# ES_3340_6HP_Rev_3.net
KiCad netlist of a schematic drawn in EAGLE
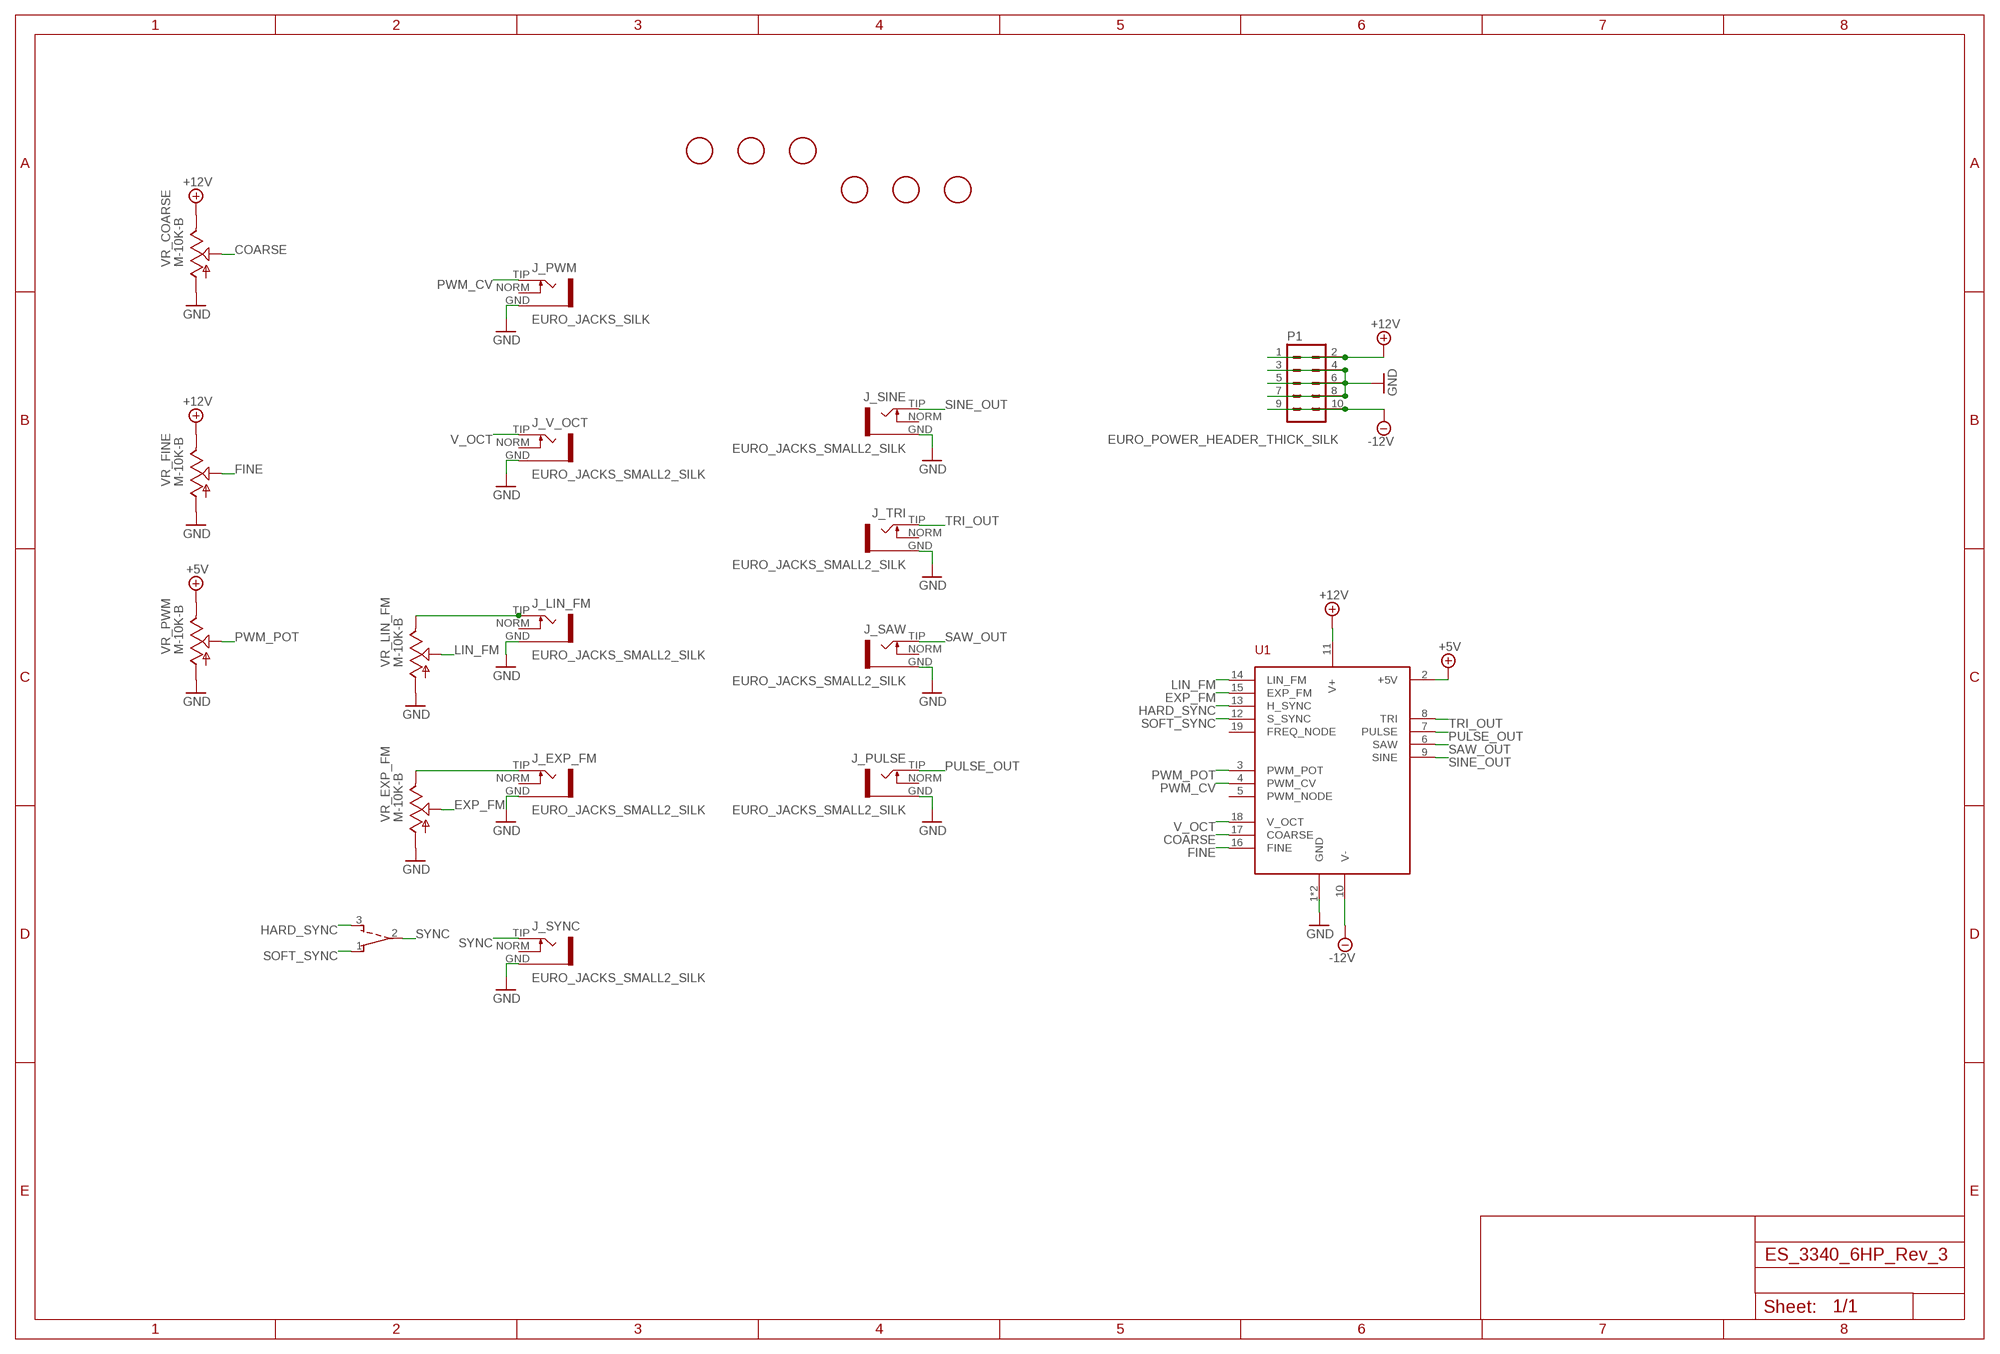
[diagram p0: schematic, sheet 1]

(export (version "E")
  (design (tool "Eeschema 10.0.6"))
  (components
    (comp (ref "FD1")
      (value "FIDUCIAL")
      (footprint "eagle-import:FIDUCIAL_1MM")
      (libsource (lib "eagle-import") (part "FIDUCIAL"))
    )
    (comp (ref "FD2")
      (value "FIDUCIAL")
      (footprint "eagle-import:FIDUCIAL_1MM")
      (libsource (lib "eagle-import") (part "FIDUCIAL"))
    )
    (comp (ref "FD3")
      (value "FIDUCIAL")
      (footprint "eagle-import:FIDUCIAL_1MM")
      (libsource (lib "eagle-import") (part "FIDUCIAL"))
    )
    (comp (ref "FD4")
      (value "FIDUCIAL")
      (footprint "eagle-import:FIDUCIAL_1MM")
      (libsource (lib "eagle-import") (part "FIDUCIAL"))
    )
    (comp (ref "FD5")
      (value "FIDUCIAL")
      (footprint "eagle-import:FIDUCIAL_1MM")
      (libsource (lib "eagle-import") (part "FIDUCIAL"))
    )
    (comp (ref "FD6")
      (value "FIDUCIAL")
      (footprint "eagle-import:FIDUCIAL_1MM")
      (libsource (lib "eagle-import") (part "FIDUCIAL"))
    )
    (comp (ref "J_EXP_FM")
      (value "EURO_JACKS_SMALL2_SILK")
      (footprint "eagle-import:S_JACK_SMALL2_SILK")
      (libsource (lib "eagle-import") (part "EURO_JACKS_SMALL2_SILK"))
    )
    (comp (ref "J_LIN_FM")
      (value "EURO_JACKS_SMALL2_SILK")
      (footprint "eagle-import:S_JACK_SMALL2_SILK")
      (libsource (lib "eagle-import") (part "EURO_JACKS_SMALL2_SILK"))
    )
    (comp (ref "J_PULSE")
      (value "EURO_JACKS_SMALL2_SILK")
      (footprint "eagle-import:S_JACK_SMALL2_SILK")
      (libsource (lib "eagle-import") (part "EURO_JACKS_SMALL2_SILK"))
    )
    (comp (ref "J_PWM")
      (value "EURO_JACKS_SILK")
      (footprint "eagle-import:S_JACK_SILK")
      (libsource (lib "eagle-import") (part "EURO_JACKS_SILK"))
    )
    (comp (ref "J_SAW")
      (value "EURO_JACKS_SMALL2_SILK")
      (footprint "eagle-import:S_JACK_SMALL2_SILK")
      (libsource (lib "eagle-import") (part "EURO_JACKS_SMALL2_SILK"))
    )
    (comp (ref "J_SINE")
      (value "EURO_JACKS_SMALL2_SILK")
      (footprint "eagle-import:S_JACK_SMALL2_SILK")
      (libsource (lib "eagle-import") (part "EURO_JACKS_SMALL2_SILK"))
    )
    (comp (ref "J_SYNC")
      (value "EURO_JACKS_SMALL2_SILK")
      (footprint "eagle-import:S_JACK_SMALL2_SILK")
      (libsource (lib "eagle-import") (part "EURO_JACKS_SMALL2_SILK"))
    )
    (comp (ref "J_TRI")
      (value "EURO_JACKS_SMALL2_SILK")
      (footprint "eagle-import:S_JACK_SMALL2_SILK")
      (libsource (lib "eagle-import") (part "EURO_JACKS_SMALL2_SILK"))
    )
    (comp (ref "J_V_OCT")
      (value "EURO_JACKS_SMALL2_SILK")
      (footprint "eagle-import:S_JACK_SMALL2_SILK")
      (libsource (lib "eagle-import") (part "EURO_JACKS_SMALL2_SILK"))
    )
    (comp (ref "P1")
      (value "EURO_POWER_HEADER_THICK_SILK")
      (footprint "eagle-import:2X5_LOCK")
      (libsource (lib "eagle-import") (part "EURO_POWER_HEADER_THICK_SILK"))
    )
    (comp (ref "SW1")
      (value "TOGGLE_ON-ON")
      (footprint "eagle-import:TOGGLE_ON-ON")
      (libsource (lib "eagle-import") (part "TOGGLE_ON-ON"))
    )
    (comp (ref "U1")
      (value "ES_3340_V2")
      (footprint "eagle-import:ES_3340_V2")
      (libsource (lib "eagle-import") (part "ES_3340_V2"))
    )
    (comp (ref "VR_COARSE")
      (value "M-10K-B")
      (footprint "eagle-import:9MM_SNAP-IN_POT_SILK")
      (libsource (lib "eagle-import") (part "POT_9MM_SNAP-IN__"))
    )
    (comp (ref "VR_EXP_FM")
      (value "M-10K-B")
      (footprint "eagle-import:9MM_SNAP-IN_POT_SILK")
      (libsource (lib "eagle-import") (part "POT_9MM_SNAP-IN__"))
    )
    (comp (ref "VR_FINE")
      (value "M-10K-B")
      (footprint "eagle-import:9MM_SNAP-IN_POT_SILK")
      (libsource (lib "eagle-import") (part "POT_9MM_SNAP-IN__"))
    )
    (comp (ref "VR_LIN_FM")
      (value "M-10K-B")
      (footprint "eagle-import:9MM_SNAP-IN_POT_SILK")
      (libsource (lib "eagle-import") (part "POT_9MM_SNAP-IN__"))
    )
    (comp (ref "VR_PWM")
      (value "M-10K-B")
      (footprint "eagle-import:9MM_SNAP-IN_POT_SILK")
      (libsource (lib "eagle-import") (part "POT_9MM_SNAP-IN__"))
    )
  )
  (nets
    (net (code "1") (name "+5V") (class "Default")
      (node (ref "U1") (pin "2") (pinfunction "+5V_2") (pintype "bidirectional"))
      (node (ref "VR_PWM") (pin "3") (pinfunction "3_3") (pintype "passive"))
    )
    (net (code "2") (name "+12V") (class "Default")
      (node (ref "P1") (pin "1") (pinfunction "10_1") (pintype "bidirectional"))
      (node (ref "P1") (pin "2") (pinfunction "9_2") (pintype "bidirectional"))
      (node (ref "U1") (pin "11") (pinfunction "V+_11") (pintype "bidirectional"))
      (node (ref "VR_COARSE") (pin "3") (pinfunction "3_3") (pintype "passive"))
      (node (ref "VR_FINE") (pin "3") (pinfunction "3_3") (pintype "passive"))
    )
    (net (code "3") (name "-12V") (class "Default")
      (node (ref "P1") (pin "10") (pinfunction "1_10") (pintype "bidirectional"))
      (node (ref "P1") (pin "9") (pinfunction "2_9") (pintype "bidirectional"))
      (node (ref "U1") (pin "10") (pinfunction "V-_10") (pintype "bidirectional"))
    )
    (net (code "4") (name "/COARSE") (class "Default")
      (node (ref "U1") (pin "17") (pinfunction "COARSE_17") (pintype "bidirectional"))
      (node (ref "VR_COARSE") (pin "2") (pinfunction "2_2") (pintype "passive"))
    )
    (net (code "5") (name "/EXP_FM") (class "Default")
      (node (ref "U1") (pin "15") (pinfunction "EXP_FM_15") (pintype "bidirectional"))
      (node (ref "VR_EXP_FM") (pin "2") (pinfunction "2_2") (pintype "passive"))
    )
    (net (code "6") (name "/FINE") (class "Default")
      (node (ref "U1") (pin "16") (pinfunction "FINE_16") (pintype "bidirectional"))
      (node (ref "VR_FINE") (pin "2") (pinfunction "2_2") (pintype "passive"))
    )
    (net (code "7") (name "/HARD_SYNC") (class "Default")
      (node (ref "SW1") (pin "3") (pinfunction "S_3") (pintype "passive"))
      (node (ref "U1") (pin "13") (pinfunction "H_SYNC_13") (pintype "bidirectional"))
    )
    (net (code "8") (name "/LIN_FM") (class "Default")
      (node (ref "U1") (pin "14") (pinfunction "LIN_FM_14") (pintype "bidirectional"))
      (node (ref "VR_LIN_FM") (pin "2") (pinfunction "2_2") (pintype "passive"))
    )
    (net (code "9") (name "/PULSE_OUT") (class "Default")
      (node (ref "J_PULSE") (pin "TIP") (pinfunction "TIP_TIP") (pintype "passive"))
      (node (ref "U1") (pin "7") (pinfunction "PULSE_7") (pintype "bidirectional"))
    )
    (net (code "10") (name "/PWM_CV") (class "Default")
      (node (ref "J_PWM") (pin "TIP") (pinfunction "TIP_TIP") (pintype "passive"))
      (node (ref "U1") (pin "4") (pinfunction "PWM_CV_4") (pintype "bidirectional"))
    )
    (net (code "11") (name "/PWM_POT") (class "Default")
      (node (ref "U1") (pin "3") (pinfunction "PWM_POT_3") (pintype "bidirectional"))
      (node (ref "VR_PWM") (pin "2") (pinfunction "2_2") (pintype "passive"))
    )
    (net (code "12") (name "/SAW_OUT") (class "Default")
      (node (ref "J_SAW") (pin "TIP") (pinfunction "TIP_TIP") (pintype "passive"))
      (node (ref "U1") (pin "6") (pinfunction "SAW_6") (pintype "bidirectional"))
    )
    (net (code "13") (name "/SINE_OUT") (class "Default")
      (node (ref "J_SINE") (pin "TIP") (pinfunction "TIP_TIP") (pintype "passive"))
      (node (ref "U1") (pin "9") (pinfunction "SINE_9") (pintype "bidirectional"))
    )
    (net (code "14") (name "/SOFT_SYNC") (class "Default")
      (node (ref "SW1") (pin "1") (pinfunction "O_1") (pintype "passive"))
      (node (ref "U1") (pin "12") (pinfunction "S_SYNC_12") (pintype "bidirectional"))
    )
    (net (code "15") (name "/SYNC") (class "Default")
      (node (ref "J_SYNC") (pin "TIP") (pinfunction "TIP_TIP") (pintype "passive"))
      (node (ref "SW1") (pin "2") (pinfunction "P_2") (pintype "passive"))
    )
    (net (code "16") (name "/TRI_OUT") (class "Default")
      (node (ref "J_TRI") (pin "TIP") (pinfunction "TIP_TIP") (pintype "passive"))
      (node (ref "U1") (pin "8") (pinfunction "TRI_8") (pintype "bidirectional"))
    )
    (net (code "17") (name "/V_OCT") (class "Default")
      (node (ref "J_V_OCT") (pin "TIP") (pinfunction "TIP_TIP") (pintype "passive"))
      (node (ref "U1") (pin "18") (pinfunction "V_OCT_18") (pintype "bidirectional"))
    )
    (net (code "18") (name "GND") (class "Default")
      (node (ref "J_EXP_FM") (pin "GND") (pinfunction "GND_GND") (pintype "passive"))
      (node (ref "J_LIN_FM") (pin "GND") (pinfunction "GND_GND") (pintype "passive"))
      (node (ref "J_PULSE") (pin "GND") (pinfunction "GND_GND") (pintype "passive"))
      (node (ref "J_PWM") (pin "GND") (pinfunction "GND_GND") (pintype "passive"))
      (node (ref "J_SAW") (pin "GND") (pinfunction "GND_GND") (pintype "passive"))
      (node (ref "J_SINE") (pin "GND") (pinfunction "GND_GND") (pintype "passive"))
      (node (ref "J_SYNC") (pin "GND") (pinfunction "GND_GND") (pintype "passive"))
      (node (ref "J_TRI") (pin "GND") (pinfunction "GND_GND") (pintype "passive"))
      (node (ref "J_V_OCT") (pin "GND") (pinfunction "GND_GND") (pintype "passive"))
      (node (ref "P1") (pin "3") (pinfunction "8_3") (pintype "bidirectional"))
      (node (ref "P1") (pin "4") (pinfunction "7_4") (pintype "bidirectional"))
      (node (ref "P1") (pin "5") (pinfunction "6_5") (pintype "bidirectional"))
      (node (ref "P1") (pin "6") (pinfunction "5_6") (pintype "bidirectional"))
      (node (ref "P1") (pin "7") (pinfunction "4_7") (pintype "bidirectional"))
      (node (ref "P1") (pin "8") (pinfunction "3_8") (pintype "bidirectional"))
      (node (ref "U1") (pin "1") (pinfunction "GND_1") (pintype "bidirectional"))
      (node (ref "U1") (pin "20") (pinfunction "GND_20") (pintype "bidirectional"))
      (node (ref "VR_COARSE") (pin "1") (pinfunction "1_1") (pintype "passive"))
      (node (ref "VR_EXP_FM") (pin "1") (pinfunction "1_1") (pintype "passive"))
      (node (ref "VR_FINE") (pin "1") (pinfunction "1_1") (pintype "passive"))
      (node (ref "VR_LIN_FM") (pin "1") (pinfunction "1_1") (pintype "passive"))
      (node (ref "VR_PWM") (pin "1") (pinfunction "1_1") (pintype "passive"))
    )
    (net (code "19") (name "Net-(J_EXP_FM-PadTIP)") (class "Default")
      (node (ref "J_EXP_FM") (pin "TIP") (pinfunction "TIP_TIP") (pintype "passive"))
      (node (ref "VR_EXP_FM") (pin "3") (pinfunction "3_3") (pintype "passive"))
    )
    (net (code "20") (name "Net-(J_LIN_FM-PadTIP)") (class "Default")
      (node (ref "J_LIN_FM") (pin "TIP") (pinfunction "TIP_TIP") (pintype "passive"))
      (node (ref "VR_LIN_FM") (pin "3") (pinfunction "3_3") (pintype "passive"))
    )
    (net (code "21") (name "unconnected-(J_EXP_FM-PadNORM)") (class "Default")
      (node (ref "J_EXP_FM") (pin "NORM") (pinfunction "NORM_NORM") (pintype "passive"))
    )
    (net (code "22") (name "unconnected-(J_LIN_FM-PadNORM)") (class "Default")
      (node (ref "J_LIN_FM") (pin "NORM") (pinfunction "NORM_NORM") (pintype "passive"))
    )
    (net (code "23") (name "unconnected-(J_PULSE-PadNORM)") (class "Default")
      (node (ref "J_PULSE") (pin "NORM") (pinfunction "NORM_NORM") (pintype "passive"))
    )
    (net (code "24") (name "unconnected-(J_PWM-PadNORM)") (class "Default")
      (node (ref "J_PWM") (pin "NORM") (pinfunction "NORM_NORM") (pintype "passive"))
    )
    (net (code "25") (name "unconnected-(J_SAW-PadNORM)") (class "Default")
      (node (ref "J_SAW") (pin "NORM") (pinfunction "NORM_NORM") (pintype "passive"))
    )
    (net (code "26") (name "unconnected-(J_SINE-PadNORM)") (class "Default")
      (node (ref "J_SINE") (pin "NORM") (pinfunction "NORM_NORM") (pintype "passive"))
    )
    (net (code "27") (name "unconnected-(J_SYNC-PadNORM)") (class "Default")
      (node (ref "J_SYNC") (pin "NORM") (pinfunction "NORM_NORM") (pintype "passive"))
    )
    (net (code "28") (name "unconnected-(J_TRI-PadNORM)") (class "Default")
      (node (ref "J_TRI") (pin "NORM") (pinfunction "NORM_NORM") (pintype "passive"))
    )
    (net (code "29") (name "unconnected-(J_V_OCT-PadNORM)") (class "Default")
      (node (ref "J_V_OCT") (pin "NORM") (pinfunction "NORM_NORM") (pintype "passive"))
    )
    (net (code "30") (name "unconnected-(U1-FREQ_NODE-Pad19)") (class "Default")
      (node (ref "U1") (pin "19") (pinfunction "FREQ_NODE_19") (pintype "bidirectional"))
    )
    (net (code "31") (name "unconnected-(U1-PWM_NODE-Pad5)") (class "Default")
      (node (ref "U1") (pin "5") (pinfunction "PWM_NODE_5") (pintype "bidirectional"))
    )
  )
)
